# BSU_ESD.net
KiCad netlist of a schematic drawn in Altium Designer
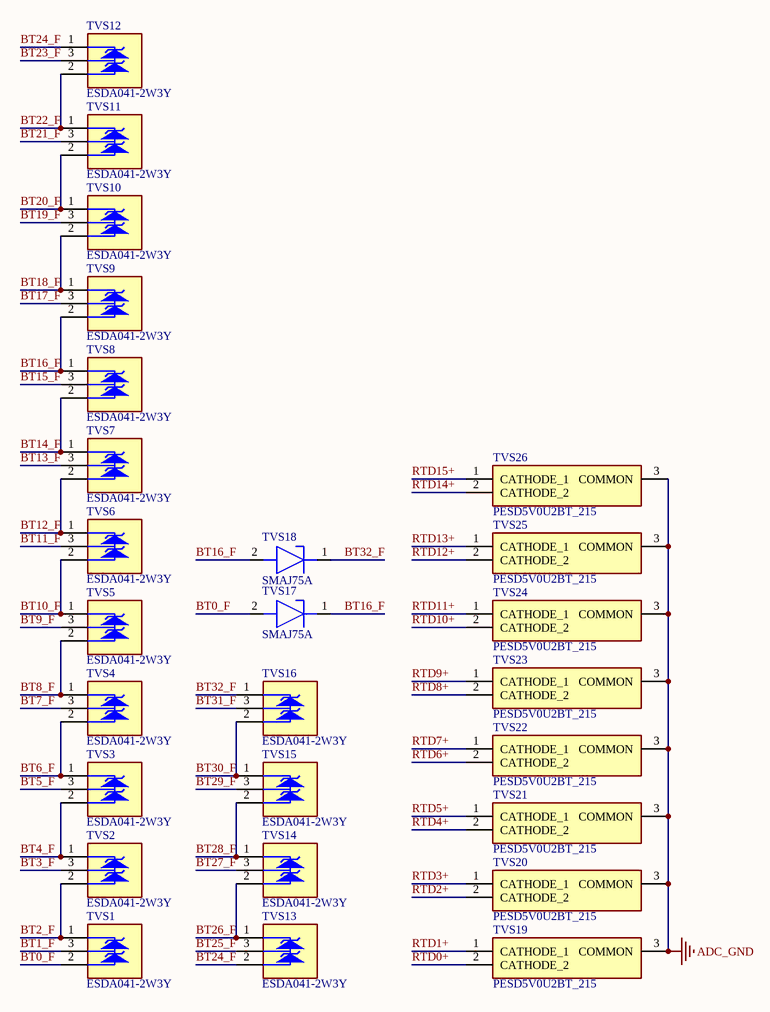
[diagram p0: BSU_ESD.SchDoc]

(export (version "E")
  (design (tool "Eeschema 10.0.6"))
  (components
    (comp (ref "TVS1")
      (value "ESDA041-2W3Y")
      (footprint "SOT323-3_ESDA041-2W3Y")
      (description "Automotive dual lines 4 V TVS for BMS in SOT323")
      (fields (field (name "MOUSER PART NUMBER") "511-ESDA041-2W3Y"))
      (libsource (lib "BMS_ShareComponentLibrary") (part "ESDA041-2W3Y"))
    )
    (comp (ref "TVS2")
      (value "ESDA041-2W3Y")
      (footprint "SOT323-3_ESDA041-2W3Y")
      (description "Automotive dual lines 4 V TVS for BMS in SOT323")
      (fields (field (name "MOUSER PART NUMBER") "511-ESDA041-2W3Y"))
      (libsource (lib "BMS_ShareComponentLibrary") (part "ESDA041-2W3Y"))
    )
    (comp (ref "TVS3")
      (value "ESDA041-2W3Y")
      (footprint "SOT323-3_ESDA041-2W3Y")
      (description "Automotive dual lines 4 V TVS for BMS in SOT323")
      (fields (field (name "MOUSER PART NUMBER") "511-ESDA041-2W3Y"))
      (libsource (lib "BMS_ShareComponentLibrary") (part "ESDA041-2W3Y"))
    )
    (comp (ref "TVS4")
      (value "ESDA041-2W3Y")
      (footprint "SOT323-3_ESDA041-2W3Y")
      (description "Automotive dual lines 4 V TVS for BMS in SOT323")
      (fields (field (name "MOUSER PART NUMBER") "511-ESDA041-2W3Y"))
      (libsource (lib "BMS_ShareComponentLibrary") (part "ESDA041-2W3Y"))
    )
    (comp (ref "TVS5")
      (value "ESDA041-2W3Y")
      (footprint "SOT323-3_ESDA041-2W3Y")
      (description "Automotive dual lines 4 V TVS for BMS in SOT323")
      (fields (field (name "MOUSER PART NUMBER") "511-ESDA041-2W3Y"))
      (libsource (lib "BMS_ShareComponentLibrary") (part "ESDA041-2W3Y"))
    )
    (comp (ref "TVS6")
      (value "ESDA041-2W3Y")
      (footprint "SOT323-3_ESDA041-2W3Y")
      (description "Automotive dual lines 4 V TVS for BMS in SOT323")
      (fields (field (name "MOUSER PART NUMBER") "511-ESDA041-2W3Y"))
      (libsource (lib "BMS_ShareComponentLibrary") (part "ESDA041-2W3Y"))
    )
    (comp (ref "TVS7")
      (value "ESDA041-2W3Y")
      (footprint "SOT323-3_ESDA041-2W3Y")
      (description "Automotive dual lines 4 V TVS for BMS in SOT323")
      (fields (field (name "MOUSER PART NUMBER") "511-ESDA041-2W3Y"))
      (libsource (lib "BMS_ShareComponentLibrary") (part "ESDA041-2W3Y"))
    )
    (comp (ref "TVS8")
      (value "ESDA041-2W3Y")
      (footprint "SOT323-3_ESDA041-2W3Y")
      (description "Automotive dual lines 4 V TVS for BMS in SOT323")
      (fields (field (name "MOUSER PART NUMBER") "511-ESDA041-2W3Y"))
      (libsource (lib "BMS_ShareComponentLibrary") (part "ESDA041-2W3Y"))
    )
    (comp (ref "TVS9")
      (value "ESDA041-2W3Y")
      (footprint "SOT323-3_ESDA041-2W3Y")
      (description "Automotive dual lines 4 V TVS for BMS in SOT323")
      (fields (field (name "MOUSER PART NUMBER") "511-ESDA041-2W3Y"))
      (libsource (lib "BMS_ShareComponentLibrary") (part "ESDA041-2W3Y"))
    )
    (comp (ref "TVS10")
      (value "ESDA041-2W3Y")
      (footprint "SOT323-3_ESDA041-2W3Y")
      (description "Automotive dual lines 4 V TVS for BMS in SOT323")
      (fields (field (name "MOUSER PART NUMBER") "511-ESDA041-2W3Y"))
      (libsource (lib "BMS_ShareComponentLibrary") (part "ESDA041-2W3Y"))
    )
    (comp (ref "TVS11")
      (value "ESDA041-2W3Y")
      (footprint "SOT323-3_ESDA041-2W3Y")
      (description "Automotive dual lines 4 V TVS for BMS in SOT323")
      (fields (field (name "MOUSER PART NUMBER") "511-ESDA041-2W3Y"))
      (libsource (lib "BMS_ShareComponentLibrary") (part "ESDA041-2W3Y"))
    )
    (comp (ref "TVS12")
      (value "ESDA041-2W3Y")
      (footprint "SOT323-3_ESDA041-2W3Y")
      (description "Automotive dual lines 4 V TVS for BMS in SOT323")
      (fields (field (name "MOUSER PART NUMBER") "511-ESDA041-2W3Y"))
      (libsource (lib "BMS_ShareComponentLibrary") (part "ESDA041-2W3Y"))
    )
    (comp (ref "TVS13")
      (value "ESDA041-2W3Y")
      (footprint "SOT323-3_ESDA041-2W3Y")
      (description "Automotive dual lines 4 V TVS for BMS in SOT323")
      (fields (field (name "MOUSER PART NUMBER") "511-ESDA041-2W3Y"))
      (libsource (lib "BMS_ShareComponentLibrary") (part "ESDA041-2W3Y"))
    )
    (comp (ref "TVS14")
      (value "ESDA041-2W3Y")
      (footprint "SOT323-3_ESDA041-2W3Y")
      (description "Automotive dual lines 4 V TVS for BMS in SOT323")
      (fields (field (name "MOUSER PART NUMBER") "511-ESDA041-2W3Y"))
      (libsource (lib "BMS_ShareComponentLibrary") (part "ESDA041-2W3Y"))
    )
    (comp (ref "TVS15")
      (value "ESDA041-2W3Y")
      (footprint "SOT323-3_ESDA041-2W3Y")
      (description "Automotive dual lines 4 V TVS for BMS in SOT323")
      (fields (field (name "MOUSER PART NUMBER") "511-ESDA041-2W3Y"))
      (libsource (lib "BMS_ShareComponentLibrary") (part "ESDA041-2W3Y"))
    )
    (comp (ref "TVS16")
      (value "ESDA041-2W3Y")
      (footprint "SOT323-3_ESDA041-2W3Y")
      (description "Automotive dual lines 4 V TVS for BMS in SOT323")
      (fields (field (name "MOUSER PART NUMBER") "511-ESDA041-2W3Y"))
      (libsource (lib "BMS_ShareComponentLibrary") (part "ESDA041-2W3Y"))
    )
    (comp (ref "TVS17")
      (value "SMAJ75A")
      (footprint "SMA_SMAJ75A")
      (description "LITTELFUSE - SMAJ75A - TVS Diode, SMAJ Series, Unidirectional, 75 V, 121 V, DO-214AC (SMA), 2 Pins")
      (fields (field (name "MOUSER PART NUMBER") "576-SMAJ75A"))
      (libsource (lib "BMS_ShareComponentLibrary") (part "SMAJ75A"))
    )
    (comp (ref "TVS18")
      (value "SMAJ75A")
      (footprint "SMA_SMAJ75A")
      (description "LITTELFUSE - SMAJ75A - TVS Diode, SMAJ Series, Unidirectional, 75 V, 121 V, DO-214AC (SMA), 2 Pins")
      (fields (field (name "MOUSER PART NUMBER") "576-SMAJ75A"))
      (libsource (lib "BMS_ShareComponentLibrary") (part "SMAJ75A"))
    )
    (comp (ref "TVS19")
      (value "PESD5V0U2BT_215")
      (footprint "SOT23-3_PESD5V0U2BT")
      (description "PESD5V0U2BT - Ultra low capacitance bidirectional double ESD protection diode")
      (fields
        (field (name "MOUSER PART NUMBER") "771-PESD5V0U2BTT/R")
        (field (name "MANUFACTURER_PART_NUMBER") "PESD5V0U2BT,215")
      )
      (libsource (lib "BMS_ShareComponentLibrary") (part "PESD5V0U2BT_215"))
    )
    (comp (ref "TVS20")
      (value "PESD5V0U2BT_215")
      (footprint "SOT23-3_PESD5V0U2BT")
      (description "PESD5V0U2BT - Ultra low capacitance bidirectional double ESD protection diode")
      (fields
        (field (name "MOUSER PART NUMBER") "771-PESD5V0U2BTT/R")
        (field (name "MANUFACTURER_PART_NUMBER") "PESD5V0U2BT,215")
      )
      (libsource (lib "BMS_ShareComponentLibrary") (part "PESD5V0U2BT_215"))
    )
    (comp (ref "TVS21")
      (value "PESD5V0U2BT_215")
      (footprint "SOT23-3_PESD5V0U2BT")
      (description "PESD5V0U2BT - Ultra low capacitance bidirectional double ESD protection diode")
      (fields
        (field (name "MOUSER PART NUMBER") "771-PESD5V0U2BTT/R")
        (field (name "MANUFACTURER_PART_NUMBER") "PESD5V0U2BT,215")
      )
      (libsource (lib "BMS_ShareComponentLibrary") (part "PESD5V0U2BT_215"))
    )
    (comp (ref "TVS22")
      (value "PESD5V0U2BT_215")
      (footprint "SOT23-3_PESD5V0U2BT")
      (description "PESD5V0U2BT - Ultra low capacitance bidirectional double ESD protection diode")
      (fields
        (field (name "MOUSER PART NUMBER") "771-PESD5V0U2BTT/R")
        (field (name "MANUFACTURER_PART_NUMBER") "PESD5V0U2BT,215")
      )
      (libsource (lib "BMS_ShareComponentLibrary") (part "PESD5V0U2BT_215"))
    )
    (comp (ref "TVS23")
      (value "PESD5V0U2BT_215")
      (footprint "SOT23-3_PESD5V0U2BT")
      (description "PESD5V0U2BT - Ultra low capacitance bidirectional double ESD protection diode")
      (fields
        (field (name "MOUSER PART NUMBER") "771-PESD5V0U2BTT/R")
        (field (name "MANUFACTURER_PART_NUMBER") "PESD5V0U2BT,215")
      )
      (libsource (lib "BMS_ShareComponentLibrary") (part "PESD5V0U2BT_215"))
    )
    (comp (ref "TVS24")
      (value "PESD5V0U2BT_215")
      (footprint "SOT23-3_PESD5V0U2BT")
      (description "PESD5V0U2BT - Ultra low capacitance bidirectional double ESD protection diode")
      (fields
        (field (name "MOUSER PART NUMBER") "771-PESD5V0U2BTT/R")
        (field (name "MANUFACTURER_PART_NUMBER") "PESD5V0U2BT,215")
      )
      (libsource (lib "BMS_ShareComponentLibrary") (part "PESD5V0U2BT_215"))
    )
    (comp (ref "TVS25")
      (value "PESD5V0U2BT_215")
      (footprint "SOT23-3_PESD5V0U2BT")
      (description "PESD5V0U2BT - Ultra low capacitance bidirectional double ESD protection diode")
      (fields
        (field (name "MOUSER PART NUMBER") "771-PESD5V0U2BTT/R")
        (field (name "MANUFACTURER_PART_NUMBER") "PESD5V0U2BT,215")
      )
      (libsource (lib "BMS_ShareComponentLibrary") (part "PESD5V0U2BT_215"))
    )
    (comp (ref "TVS26")
      (value "PESD5V0U2BT_215")
      (footprint "SOT23-3_PESD5V0U2BT")
      (description "PESD5V0U2BT - Ultra low capacitance bidirectional double ESD protection diode")
      (fields
        (field (name "MOUSER PART NUMBER") "771-PESD5V0U2BTT/R")
        (field (name "MANUFACTURER_PART_NUMBER") "PESD5V0U2BT,215")
      )
      (libsource (lib "BMS_ShareComponentLibrary") (part "PESD5V0U2BT_215"))
    )
  )
  (nets
    (net (code "1") (name "/BT0_F") (class "Default")
      (node (ref "TVS1") (pin "2") (pinfunction "A2_2") (pintype "passive"))
      (node (ref "TVS17") (pin "2") (pinfunction "A_2") (pintype "passive"))
    )
    (net (code "2") (name "/BT1_F") (class "Default")
      (node (ref "TVS1") (pin "3") (pinfunction "A1_/K2_3") (pintype "passive"))
    )
    (net (code "3") (name "/BT2_F") (class "Default")
      (node (ref "TVS1") (pin "1") (pinfunction "K1_1") (pintype "passive"))
      (node (ref "TVS2") (pin "2") (pinfunction "A2_2") (pintype "passive"))
    )
    (net (code "4") (name "/BT3_F") (class "Default")
      (node (ref "TVS2") (pin "3") (pinfunction "A1_/K2_3") (pintype "passive"))
    )
    (net (code "5") (name "/BT4_F") (class "Default")
      (node (ref "TVS2") (pin "1") (pinfunction "K1_1") (pintype "passive"))
      (node (ref "TVS3") (pin "2") (pinfunction "A2_2") (pintype "passive"))
    )
    (net (code "6") (name "/BT5_F") (class "Default")
      (node (ref "TVS3") (pin "3") (pinfunction "A1_/K2_3") (pintype "passive"))
    )
    (net (code "7") (name "/BT6_F") (class "Default")
      (node (ref "TVS3") (pin "1") (pinfunction "K1_1") (pintype "passive"))
      (node (ref "TVS4") (pin "2") (pinfunction "A2_2") (pintype "passive"))
    )
    (net (code "8") (name "/BT7_F") (class "Default")
      (node (ref "TVS4") (pin "3") (pinfunction "A1_/K2_3") (pintype "passive"))
    )
    (net (code "9") (name "/BT8_F") (class "Default")
      (node (ref "TVS4") (pin "1") (pinfunction "K1_1") (pintype "passive"))
      (node (ref "TVS5") (pin "2") (pinfunction "A2_2") (pintype "passive"))
    )
    (net (code "10") (name "/BT9_F") (class "Default")
      (node (ref "TVS5") (pin "3") (pinfunction "A1_/K2_3") (pintype "passive"))
    )
    (net (code "11") (name "/BT10_F") (class "Default")
      (node (ref "TVS5") (pin "1") (pinfunction "K1_1") (pintype "passive"))
      (node (ref "TVS6") (pin "2") (pinfunction "A2_2") (pintype "passive"))
    )
    (net (code "12") (name "/BT11_F") (class "Default")
      (node (ref "TVS6") (pin "3") (pinfunction "A1_/K2_3") (pintype "passive"))
    )
    (net (code "13") (name "/BT12_F") (class "Default")
      (node (ref "TVS6") (pin "1") (pinfunction "K1_1") (pintype "passive"))
      (node (ref "TVS7") (pin "2") (pinfunction "A2_2") (pintype "passive"))
    )
    (net (code "14") (name "/BT13_F") (class "Default")
      (node (ref "TVS7") (pin "3") (pinfunction "A1_/K2_3") (pintype "passive"))
    )
    (net (code "15") (name "/BT14_F") (class "Default")
      (node (ref "TVS7") (pin "1") (pinfunction "K1_1") (pintype "passive"))
      (node (ref "TVS8") (pin "2") (pinfunction "A2_2") (pintype "passive"))
    )
    (net (code "16") (name "/BT15_F") (class "Default")
      (node (ref "TVS8") (pin "3") (pinfunction "A1_/K2_3") (pintype "passive"))
    )
    (net (code "17") (name "/BT16_F") (class "Default")
      (node (ref "TVS17") (pin "1") (pinfunction "K_1") (pintype "passive"))
      (node (ref "TVS18") (pin "2") (pinfunction "A_2") (pintype "passive"))
      (node (ref "TVS8") (pin "1") (pinfunction "K1_1") (pintype "passive"))
      (node (ref "TVS9") (pin "2") (pinfunction "A2_2") (pintype "passive"))
    )
    (net (code "18") (name "/BT17_F") (class "Default")
      (node (ref "TVS9") (pin "3") (pinfunction "A1_/K2_3") (pintype "passive"))
    )
    (net (code "19") (name "/BT18_F") (class "Default")
      (node (ref "TVS10") (pin "2") (pinfunction "A2_2") (pintype "passive"))
      (node (ref "TVS9") (pin "1") (pinfunction "K1_1") (pintype "passive"))
    )
    (net (code "20") (name "/BT19_F") (class "Default")
      (node (ref "TVS10") (pin "3") (pinfunction "A1_/K2_3") (pintype "passive"))
    )
    (net (code "21") (name "/BT20_F") (class "Default")
      (node (ref "TVS10") (pin "1") (pinfunction "K1_1") (pintype "passive"))
      (node (ref "TVS11") (pin "2") (pinfunction "A2_2") (pintype "passive"))
    )
    (net (code "22") (name "/BT21_F") (class "Default")
      (node (ref "TVS11") (pin "3") (pinfunction "A1_/K2_3") (pintype "passive"))
    )
    (net (code "23") (name "/BT22_F") (class "Default")
      (node (ref "TVS11") (pin "1") (pinfunction "K1_1") (pintype "passive"))
      (node (ref "TVS12") (pin "2") (pinfunction "A2_2") (pintype "passive"))
    )
    (net (code "24") (name "/BT23_F") (class "Default")
      (node (ref "TVS12") (pin "3") (pinfunction "A1_/K2_3") (pintype "passive"))
    )
    (net (code "25") (name "/BT24_F") (class "Default")
      (node (ref "TVS12") (pin "1") (pinfunction "K1_1") (pintype "passive"))
      (node (ref "TVS13") (pin "2") (pinfunction "A2_2") (pintype "passive"))
    )
    (net (code "26") (name "/BT25_F") (class "Default")
      (node (ref "TVS13") (pin "3") (pinfunction "A1_/K2_3") (pintype "passive"))
    )
    (net (code "27") (name "/BT26_F") (class "Default")
      (node (ref "TVS13") (pin "1") (pinfunction "K1_1") (pintype "passive"))
      (node (ref "TVS14") (pin "2") (pinfunction "A2_2") (pintype "passive"))
    )
    (net (code "28") (name "/BT27_F") (class "Default")
      (node (ref "TVS14") (pin "3") (pinfunction "A1_/K2_3") (pintype "passive"))
    )
    (net (code "29") (name "/BT28_F") (class "Default")
      (node (ref "TVS14") (pin "1") (pinfunction "K1_1") (pintype "passive"))
      (node (ref "TVS15") (pin "2") (pinfunction "A2_2") (pintype "passive"))
    )
    (net (code "30") (name "/BT29_F") (class "Default")
      (node (ref "TVS15") (pin "3") (pinfunction "A1_/K2_3") (pintype "passive"))
    )
    (net (code "31") (name "/BT30_F") (class "Default")
      (node (ref "TVS15") (pin "1") (pinfunction "K1_1") (pintype "passive"))
      (node (ref "TVS16") (pin "2") (pinfunction "A2_2") (pintype "passive"))
    )
    (net (code "32") (name "/BT31_F") (class "Default")
      (node (ref "TVS16") (pin "3") (pinfunction "A1_/K2_3") (pintype "passive"))
    )
    (net (code "33") (name "/BT32_F") (class "Default")
      (node (ref "TVS16") (pin "1") (pinfunction "K1_1") (pintype "passive"))
      (node (ref "TVS18") (pin "1") (pinfunction "K_1") (pintype "passive"))
    )
    (net (code "34") (name "/RTD0+") (class "Default")
      (node (ref "TVS19") (pin "2") (pinfunction "CATHODE_2_2") (pintype "passive"))
    )
    (net (code "35") (name "/RTD1+") (class "Default")
      (node (ref "TVS19") (pin "1") (pinfunction "CATHODE_1_1") (pintype "passive"))
    )
    (net (code "36") (name "/RTD2+") (class "Default")
      (node (ref "TVS20") (pin "2") (pinfunction "CATHODE_2_2") (pintype "passive"))
    )
    (net (code "37") (name "/RTD3+") (class "Default")
      (node (ref "TVS20") (pin "1") (pinfunction "CATHODE_1_1") (pintype "passive"))
    )
    (net (code "38") (name "/RTD4+") (class "Default")
      (node (ref "TVS21") (pin "2") (pinfunction "CATHODE_2_2") (pintype "passive"))
    )
    (net (code "39") (name "/RTD5+") (class "Default")
      (node (ref "TVS21") (pin "1") (pinfunction "CATHODE_1_1") (pintype "passive"))
    )
    (net (code "40") (name "/RTD6+") (class "Default")
      (node (ref "TVS22") (pin "2") (pinfunction "CATHODE_2_2") (pintype "passive"))
    )
    (net (code "41") (name "/RTD7+") (class "Default")
      (node (ref "TVS22") (pin "1") (pinfunction "CATHODE_1_1") (pintype "passive"))
    )
    (net (code "42") (name "/RTD8+") (class "Default")
      (node (ref "TVS23") (pin "2") (pinfunction "CATHODE_2_2") (pintype "passive"))
    )
    (net (code "43") (name "/RTD9+") (class "Default")
      (node (ref "TVS23") (pin "1") (pinfunction "CATHODE_1_1") (pintype "passive"))
    )
    (net (code "44") (name "/RTD10+") (class "Default")
      (node (ref "TVS24") (pin "2") (pinfunction "CATHODE_2_2") (pintype "passive"))
    )
    (net (code "45") (name "/RTD11+") (class "Default")
      (node (ref "TVS24") (pin "1") (pinfunction "CATHODE_1_1") (pintype "passive"))
    )
    (net (code "46") (name "/RTD12+") (class "Default")
      (node (ref "TVS25") (pin "2") (pinfunction "CATHODE_2_2") (pintype "passive"))
    )
    (net (code "47") (name "/RTD13+") (class "Default")
      (node (ref "TVS25") (pin "1") (pinfunction "CATHODE_1_1") (pintype "passive"))
    )
    (net (code "48") (name "/RTD14+") (class "Default")
      (node (ref "TVS26") (pin "2") (pinfunction "CATHODE_2_2") (pintype "passive"))
    )
    (net (code "49") (name "/RTD15+") (class "Default")
      (node (ref "TVS26") (pin "1") (pinfunction "CATHODE_1_1") (pintype "passive"))
    )
    (net (code "50") (name "ADC_GND") (class "Default")
      (node (ref "TVS19") (pin "3") (pinfunction "COMMON_3") (pintype "passive"))
      (node (ref "TVS20") (pin "3") (pinfunction "COMMON_3") (pintype "passive"))
      (node (ref "TVS21") (pin "3") (pinfunction "COMMON_3") (pintype "passive"))
      (node (ref "TVS22") (pin "3") (pinfunction "COMMON_3") (pintype "passive"))
      (node (ref "TVS23") (pin "3") (pinfunction "COMMON_3") (pintype "passive"))
      (node (ref "TVS24") (pin "3") (pinfunction "COMMON_3") (pintype "passive"))
      (node (ref "TVS25") (pin "3") (pinfunction "COMMON_3") (pintype "passive"))
      (node (ref "TVS26") (pin "3") (pinfunction "COMMON_3") (pintype "passive"))
    )
  )
)
